# PQS42019_1_v5.net
KiCad netlist of a schematic drawn in EAGLE
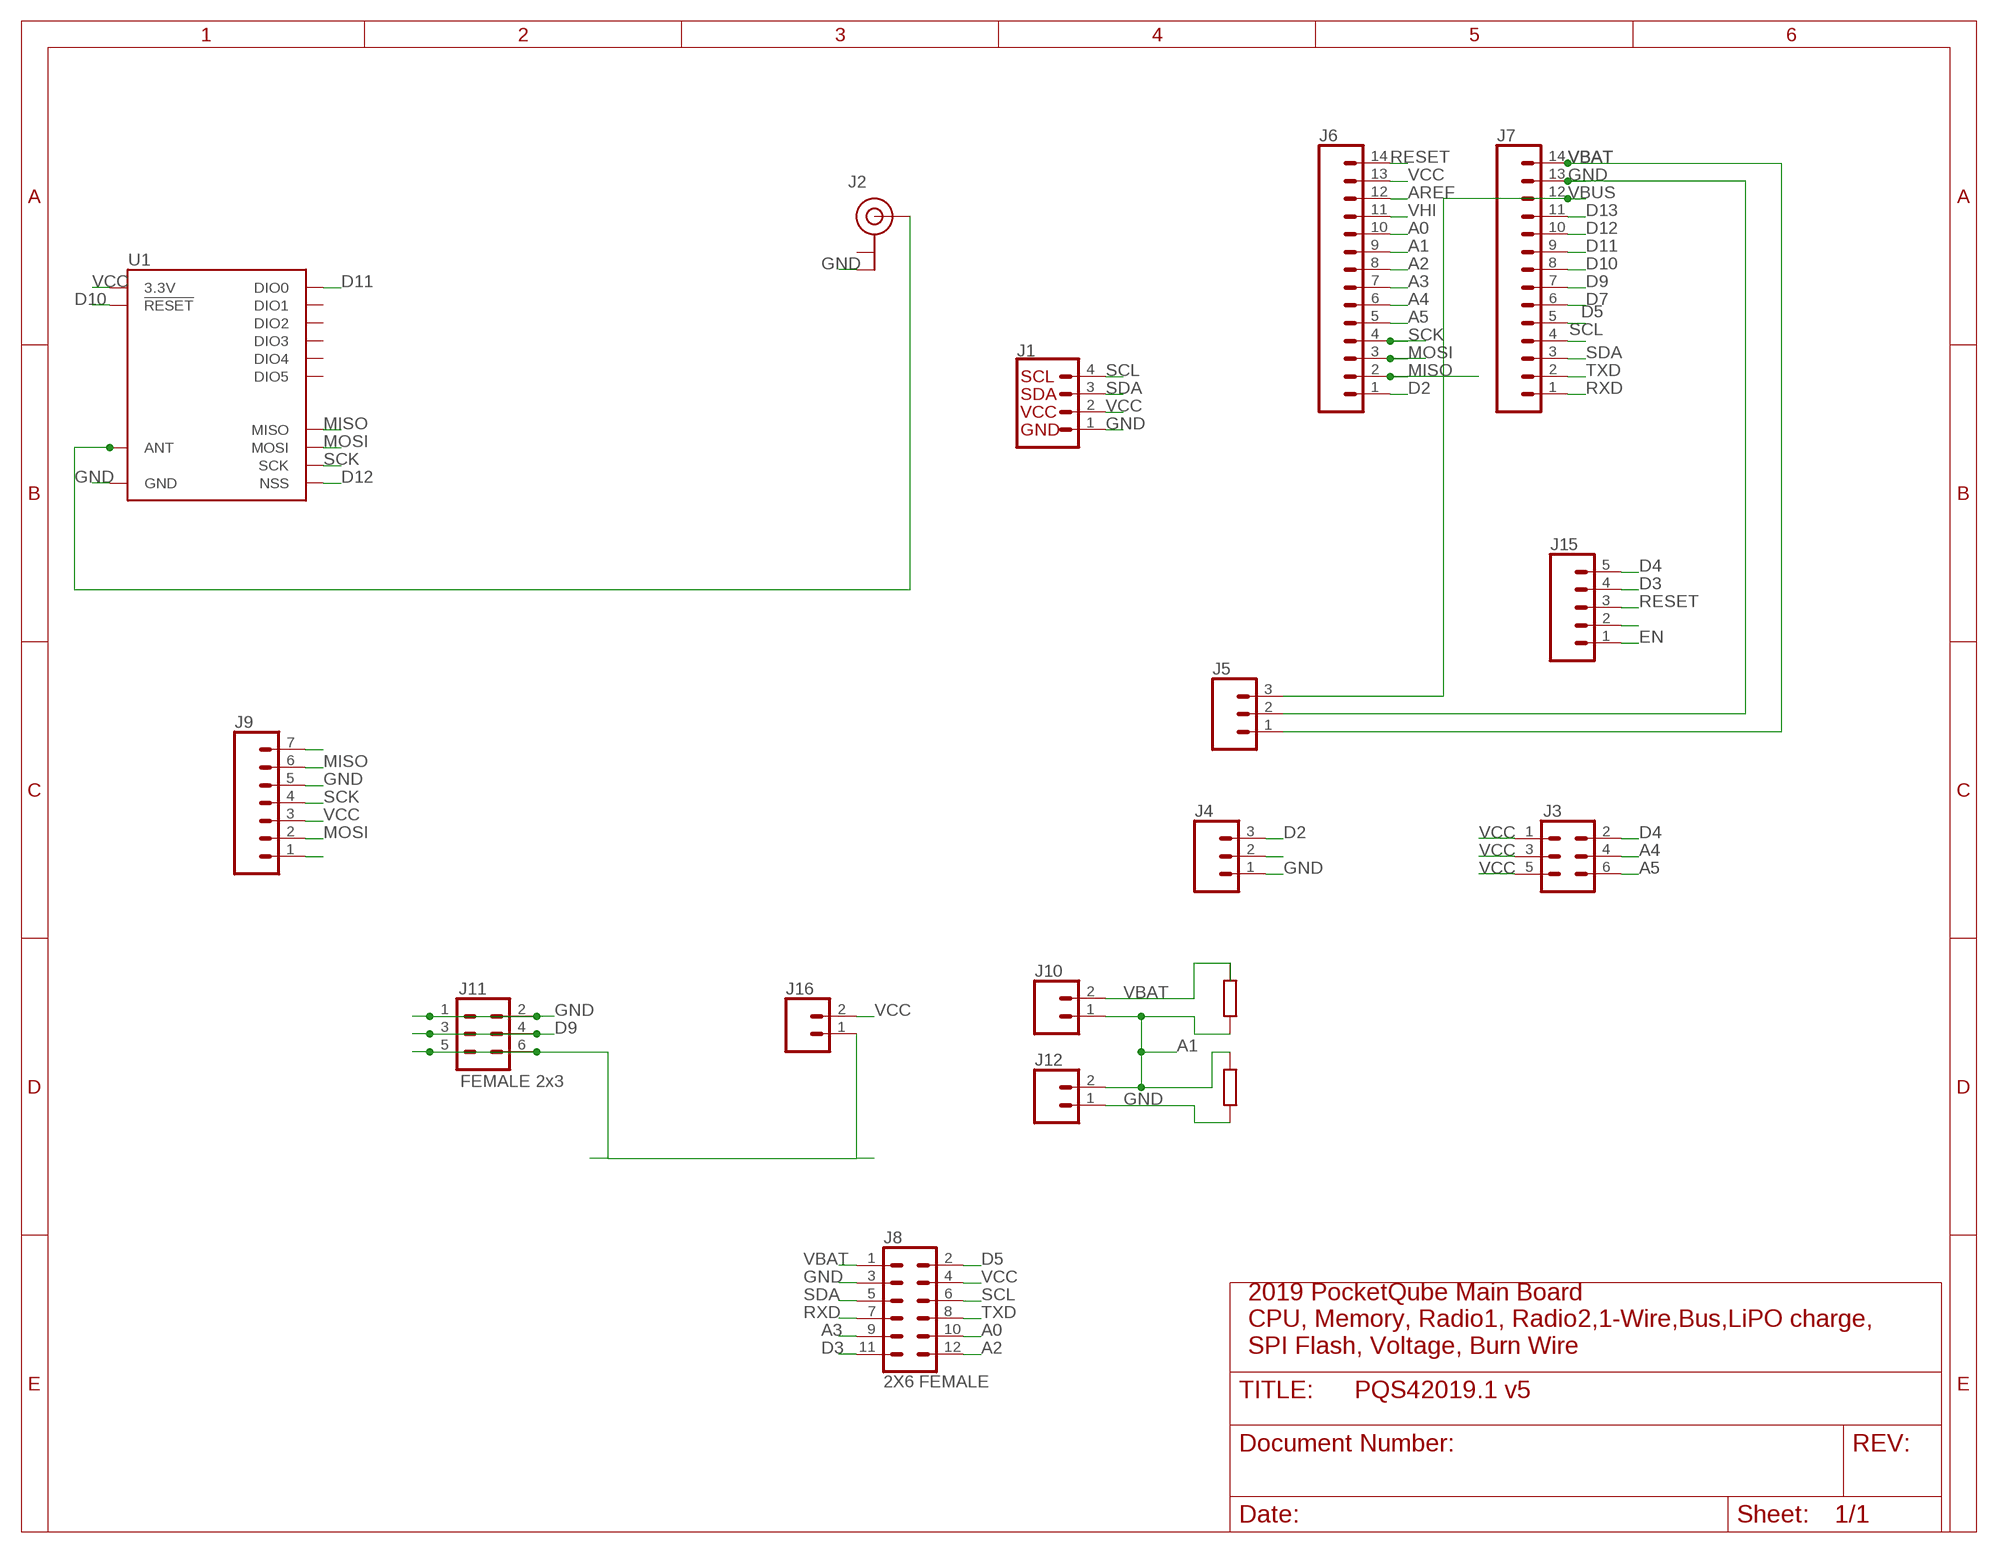
[diagram p0: schematic, sheet 1]

(export (version "E")
  (design (tool "Eeschema 10.0.6"))
  (components
    (comp (ref "J1")
      (value "QWIIC_CONNECTORJS-1MM")
      (footprint "eagle-import:1X04_1MM_RA")
      (libsource (lib "eagle-import") (part "QWIIC_CONNECTORJS-1MM"))
    )
    (comp (ref "J2")
      (value "U.FL")
      (footprint "eagle-import:U.FL")
      (libsource (lib "eagle-import") (part "U.FL"))
    )
    (comp (ref "J3")
      (value "CONN_03X2NO_SILK")
      (footprint "eagle-import:2X3-NS")
      (libsource (lib "eagle-import") (part "CONN_03X2NO_SILK"))
    )
    (comp (ref "J4")
      (value "CONN_03")
      (footprint "eagle-import:1X03")
      (libsource (lib "eagle-import") (part "CONN_03"))
    )
    (comp (ref "J5")
      (value "CONN_03")
      (footprint "eagle-import:1X03")
      (libsource (lib "eagle-import") (part "CONN_03"))
    )
    (comp (ref "J6")
      (value "CONN_14")
      (footprint "eagle-import:1X14")
      (libsource (lib "eagle-import") (part "CONN_14"))
    )
    (comp (ref "J7")
      (value "CONN_14")
      (footprint "eagle-import:1X14")
      (libsource (lib "eagle-import") (part "CONN_14"))
    )
    (comp (ref "J8")
      (value "2X6 FEMALE")
      (footprint "eagle-import:2X6")
      (libsource (lib "eagle-import") (part "CONN_06X2PTH_FEMALE"))
    )
    (comp (ref "J9")
      (value "CONN_07")
      (footprint "eagle-import:1X07")
      (libsource (lib "eagle-import") (part "CONN_07"))
    )
    (comp (ref "J10")
      (value "CONN_02")
      (footprint "eagle-import:1X02")
      (libsource (lib "eagle-import") (part "CONN_02"))
    )
    (comp (ref "J11")
      (value "FEMALE 2x3")
      (footprint "eagle-import:2X3")
      (libsource (lib "eagle-import") (part "CONN_03X2FEMALE"))
    )
    (comp (ref "J12")
      (value "CONN_02")
      (footprint "eagle-import:1X02")
      (libsource (lib "eagle-import") (part "CONN_02"))
    )
    (comp (ref "J15")
      (value "CONN_05")
      (footprint "eagle-import:1X05")
      (libsource (lib "eagle-import") (part "CONN_05"))
    )
    (comp (ref "J16")
      (value "CONN_02")
      (footprint "eagle-import:1X02")
      (libsource (lib "eagle-import") (part "CONN_02"))
    )
    (comp (ref "U1")
      (value "RFM95W")
      (footprint "eagle-import:RFM95_96_97_98W")
      (libsource (lib "eagle-import") (part "RFM95W"))
    )
  )
  (nets
    (net (code "1") (name "/A0") (class "Default")
      (node (ref "J6") (pin "10") (pinfunction "10_10") (pintype "passive"))
      (node (ref "J8") (pin "10") (pinfunction "10_10") (pintype "passive"))
    )
    (net (code "2") (name "/A1") (class "Default")
      (node (ref "J10") (pin "1") (pinfunction "1_1") (pintype "passive"))
      (node (ref "J12") (pin "2") (pinfunction "2_2") (pintype "passive"))
      (node (ref "J6") (pin "9") (pinfunction "9_9") (pintype "passive"))
    )
    (net (code "3") (name "/A2") (class "Default")
      (node (ref "J6") (pin "8") (pinfunction "8_8") (pintype "passive"))
      (node (ref "J8") (pin "12") (pinfunction "12_12") (pintype "passive"))
    )
    (net (code "4") (name "/A3") (class "Default")
      (node (ref "J6") (pin "7") (pinfunction "7_7") (pintype "passive"))
      (node (ref "J8") (pin "9") (pinfunction "9_9") (pintype "passive"))
    )
    (net (code "5") (name "/A4") (class "Default")
      (node (ref "J3") (pin "4") (pinfunction "4_4") (pintype "bidirectional"))
      (node (ref "J6") (pin "6") (pinfunction "6_6") (pintype "passive"))
    )
    (net (code "6") (name "/A5") (class "Default")
      (node (ref "J3") (pin "6") (pinfunction "6_6") (pintype "bidirectional"))
      (node (ref "J6") (pin "5") (pinfunction "5_5") (pintype "passive"))
    )
    (net (code "7") (name "/AREF") (class "Default")
      (node (ref "J6") (pin "12") (pinfunction "12_12") (pintype "passive"))
    )
    (net (code "8") (name "/D2") (class "Default")
      (node (ref "J4") (pin "3") (pinfunction "3_3") (pintype "passive"))
      (node (ref "J6") (pin "1") (pinfunction "1_1") (pintype "passive"))
    )
    (net (code "9") (name "/D3") (class "Default")
      (node (ref "J15") (pin "4") (pinfunction "4_4") (pintype "passive"))
      (node (ref "J8") (pin "11") (pinfunction "11_11") (pintype "passive"))
    )
    (net (code "10") (name "/D4") (class "Default")
      (node (ref "J15") (pin "5") (pinfunction "5_5") (pintype "passive"))
      (node (ref "J3") (pin "2") (pinfunction "2_2") (pintype "bidirectional"))
    )
    (net (code "11") (name "/D5") (class "Default")
      (node (ref "J7") (pin "5") (pinfunction "5_5") (pintype "passive"))
      (node (ref "J8") (pin "2") (pinfunction "2_2") (pintype "passive"))
    )
    (net (code "12") (name "/D7") (class "Default")
      (node (ref "J7") (pin "6") (pinfunction "6_6") (pintype "passive"))
      (node (ref "J9") (pin "1") (pinfunction "1_1") (pintype "passive"))
    )
    (net (code "13") (name "/D9") (class "Default")
      (node (ref "J11") (pin "3") (pinfunction "3_3") (pintype "bidirectional"))
      (node (ref "J11") (pin "4") (pinfunction "4_4") (pintype "bidirectional"))
      (node (ref "J7") (pin "7") (pinfunction "7_7") (pintype "passive"))
    )
    (net (code "14") (name "/D10") (class "Default")
      (node (ref "J7") (pin "8") (pinfunction "8_8") (pintype "passive"))
      (node (ref "U1") (pin "!RESET") (pinfunction "~{RESET}_!RESET") (pintype "bidirectional"))
    )
    (net (code "15") (name "/D11") (class "Default")
      (node (ref "J7") (pin "9") (pinfunction "9_9") (pintype "passive"))
      (node (ref "U1") (pin "DIO0") (pinfunction "DIO0_DIO0") (pintype "bidirectional"))
    )
    (net (code "16") (name "/D12") (class "Default")
      (node (ref "J7") (pin "10") (pinfunction "10_10") (pintype "passive"))
      (node (ref "U1") (pin "NSS") (pinfunction "NSS_NSS") (pintype "bidirectional"))
    )
    (net (code "17") (name "/D13") (class "Default")
      (node (ref "J7") (pin "11") (pinfunction "11_11") (pintype "passive"))
    )
    (net (code "18") (name "/EN") (class "Default")
      (node (ref "J15") (pin "1") (pinfunction "1_1") (pintype "passive"))
    )
    (net (code "19") (name "/GND") (class "Default")
      (node (ref "J1") (pin "1") (pinfunction "GND_1") (pintype "power_in"))
      (node (ref "J11") (pin "1") (pinfunction "1_1") (pintype "bidirectional"))
      (node (ref "J11") (pin "2") (pinfunction "2_2") (pintype "bidirectional"))
      (node (ref "J12") (pin "1") (pinfunction "1_1") (pintype "passive"))
      (node (ref "J2") (pin "2") (pinfunction "GND_2") (pintype "bidirectional"))
      (node (ref "J4") (pin "1") (pinfunction "1_1") (pintype "passive"))
      (node (ref "J5") (pin "2") (pinfunction "2_2") (pintype "passive"))
      (node (ref "J7") (pin "13") (pinfunction "13_13") (pintype "passive"))
      (node (ref "J8") (pin "3") (pinfunction "3_3") (pintype "passive"))
      (node (ref "J9") (pin "5") (pinfunction "5_5") (pintype "passive"))
      (node (ref "U1") (pin "GND@1") (pinfunction "GND_GND@1") (pintype "bidirectional"))
      (node (ref "U1") (pin "GND@2") (pinfunction "GND_GND@2") (pintype "bidirectional"))
      (node (ref "U1") (pin "GND@3") (pinfunction "GND_GND@3") (pintype "bidirectional"))
    )
    (net (code "20") (name "/MISO") (class "Default")
      (node (ref "J6") (pin "2") (pinfunction "2_2") (pintype "passive"))
      (node (ref "J9") (pin "6") (pinfunction "6_6") (pintype "passive"))
      (node (ref "U1") (pin "MISO") (pinfunction "MISO_MISO") (pintype "bidirectional"))
    )
    (net (code "21") (name "/MOSI") (class "Default")
      (node (ref "J6") (pin "3") (pinfunction "3_3") (pintype "passive"))
      (node (ref "J9") (pin "2") (pinfunction "2_2") (pintype "passive"))
      (node (ref "U1") (pin "MOSI") (pinfunction "MOSI_MOSI") (pintype "bidirectional"))
    )
    (net (code "22") (name "/RESET") (class "Default")
      (node (ref "J15") (pin "3") (pinfunction "3_3") (pintype "passive"))
      (node (ref "J6") (pin "14") (pinfunction "14_14") (pintype "passive"))
    )
    (net (code "23") (name "/RXD") (class "Default")
      (node (ref "J7") (pin "1") (pinfunction "1_1") (pintype "passive"))
      (node (ref "J8") (pin "7") (pinfunction "7_7") (pintype "passive"))
    )
    (net (code "24") (name "/SCK") (class "Default")
      (node (ref "J6") (pin "4") (pinfunction "4_4") (pintype "passive"))
      (node (ref "J9") (pin "4") (pinfunction "4_4") (pintype "passive"))
      (node (ref "U1") (pin "SCK") (pinfunction "SCK_SCK") (pintype "bidirectional"))
    )
    (net (code "25") (name "/SCL") (class "Default")
      (node (ref "J1") (pin "4") (pinfunction "SCL_4") (pintype "passive"))
      (node (ref "J7") (pin "4") (pinfunction "4_4") (pintype "passive"))
      (node (ref "J8") (pin "6") (pinfunction "6_6") (pintype "passive"))
    )
    (net (code "26") (name "/SDA") (class "Default")
      (node (ref "J1") (pin "3") (pinfunction "SDA_3") (pintype "passive"))
      (node (ref "J7") (pin "3") (pinfunction "3_3") (pintype "passive"))
      (node (ref "J8") (pin "5") (pinfunction "5_5") (pintype "passive"))
    )
    (net (code "27") (name "/TXD") (class "Default")
      (node (ref "J7") (pin "2") (pinfunction "2_2") (pintype "passive"))
      (node (ref "J8") (pin "8") (pinfunction "8_8") (pintype "passive"))
    )
    (net (code "28") (name "/VBAT") (class "Default")
      (node (ref "J10") (pin "2") (pinfunction "2_2") (pintype "passive"))
      (node (ref "J5") (pin "1") (pinfunction "1_1") (pintype "passive"))
      (node (ref "J7") (pin "14") (pinfunction "14_14") (pintype "passive"))
      (node (ref "J8") (pin "1") (pinfunction "1_1") (pintype "passive"))
    )
    (net (code "29") (name "/VBUS") (class "Default")
      (node (ref "J5") (pin "3") (pinfunction "3_3") (pintype "passive"))
      (node (ref "J7") (pin "12") (pinfunction "12_12") (pintype "passive"))
    )
    (net (code "30") (name "/VCC") (class "Default")
      (node (ref "J1") (pin "2") (pinfunction "VCC_2") (pintype "power_in"))
      (node (ref "J16") (pin "2") (pinfunction "2_2") (pintype "passive"))
      (node (ref "J3") (pin "1") (pinfunction "1_1") (pintype "bidirectional"))
      (node (ref "J3") (pin "3") (pinfunction "3_3") (pintype "bidirectional"))
      (node (ref "J3") (pin "5") (pinfunction "5_5") (pintype "bidirectional"))
      (node (ref "J6") (pin "13") (pinfunction "13_13") (pintype "passive"))
      (node (ref "J8") (pin "4") (pinfunction "4_4") (pintype "passive"))
      (node (ref "J9") (pin "3") (pinfunction "3_3") (pintype "passive"))
      (node (ref "U1") (pin "3.3V") (pinfunction "3.3V_3.3V") (pintype "bidirectional"))
    )
    (net (code "31") (name "/VHI") (class "Default")
      (node (ref "J6") (pin "11") (pinfunction "11_11") (pintype "passive"))
    )
    (net (code "32") (name "Net-(J2-SIGNAL)") (class "Default")
      (node (ref "J2") (pin "FEED") (pinfunction "SIGNAL_FEED") (pintype "bidirectional"))
      (node (ref "U1") (pin "ANT") (pinfunction "ANT_ANT") (pintype "bidirectional"))
    )
    (net (code "33") (name "Net-(J11-Pad5)") (class "Default")
      (node (ref "J11") (pin "5") (pinfunction "5_5") (pintype "bidirectional"))
      (node (ref "J11") (pin "6") (pinfunction "6_6") (pintype "bidirectional"))
      (node (ref "J16") (pin "1") (pinfunction "1_1") (pintype "passive"))
    )
    (net (code "34") (name "unconnected-(J2-GND-Pad1)") (class "Default")
      (node (ref "J2") (pin "1") (pinfunction "GND_1") (pintype "bidirectional"))
    )
    (net (code "35") (name "unconnected-(J4-Pad2)") (class "Default")
      (node (ref "J4") (pin "2") (pinfunction "2_2") (pintype "passive"))
    )
    (net (code "36") (name "unconnected-(J9-Pad7)") (class "Default")
      (node (ref "J9") (pin "7") (pinfunction "7_7") (pintype "passive"))
    )
    (net (code "37") (name "unconnected-(J15-Pad2)") (class "Default")
      (node (ref "J15") (pin "2") (pinfunction "2_2") (pintype "passive"))
    )
    (net (code "38") (name "unconnected-(U1-PadDIO1)") (class "Default")
      (node (ref "U1") (pin "DIO1") (pinfunction "DIO1_DIO1") (pintype "bidirectional"))
    )
    (net (code "39") (name "unconnected-(U1-PadDIO2)") (class "Default")
      (node (ref "U1") (pin "DIO2") (pinfunction "DIO2_DIO2") (pintype "bidirectional"))
    )
    (net (code "40") (name "unconnected-(U1-PadDIO3)") (class "Default")
      (node (ref "U1") (pin "DIO3") (pinfunction "DIO3_DIO3") (pintype "bidirectional"))
    )
    (net (code "41") (name "unconnected-(U1-PadDIO4)") (class "Default")
      (node (ref "U1") (pin "DIO4") (pinfunction "DIO4_DIO4") (pintype "bidirectional"))
    )
    (net (code "42") (name "unconnected-(U1-PadDIO5)") (class "Default")
      (node (ref "U1") (pin "DIO5") (pinfunction "DIO5_DIO5") (pintype "bidirectional"))
    )
  )
)
